# Schematic_v1_2.net
KiCad netlist of a schematic drawn in EasyEDA
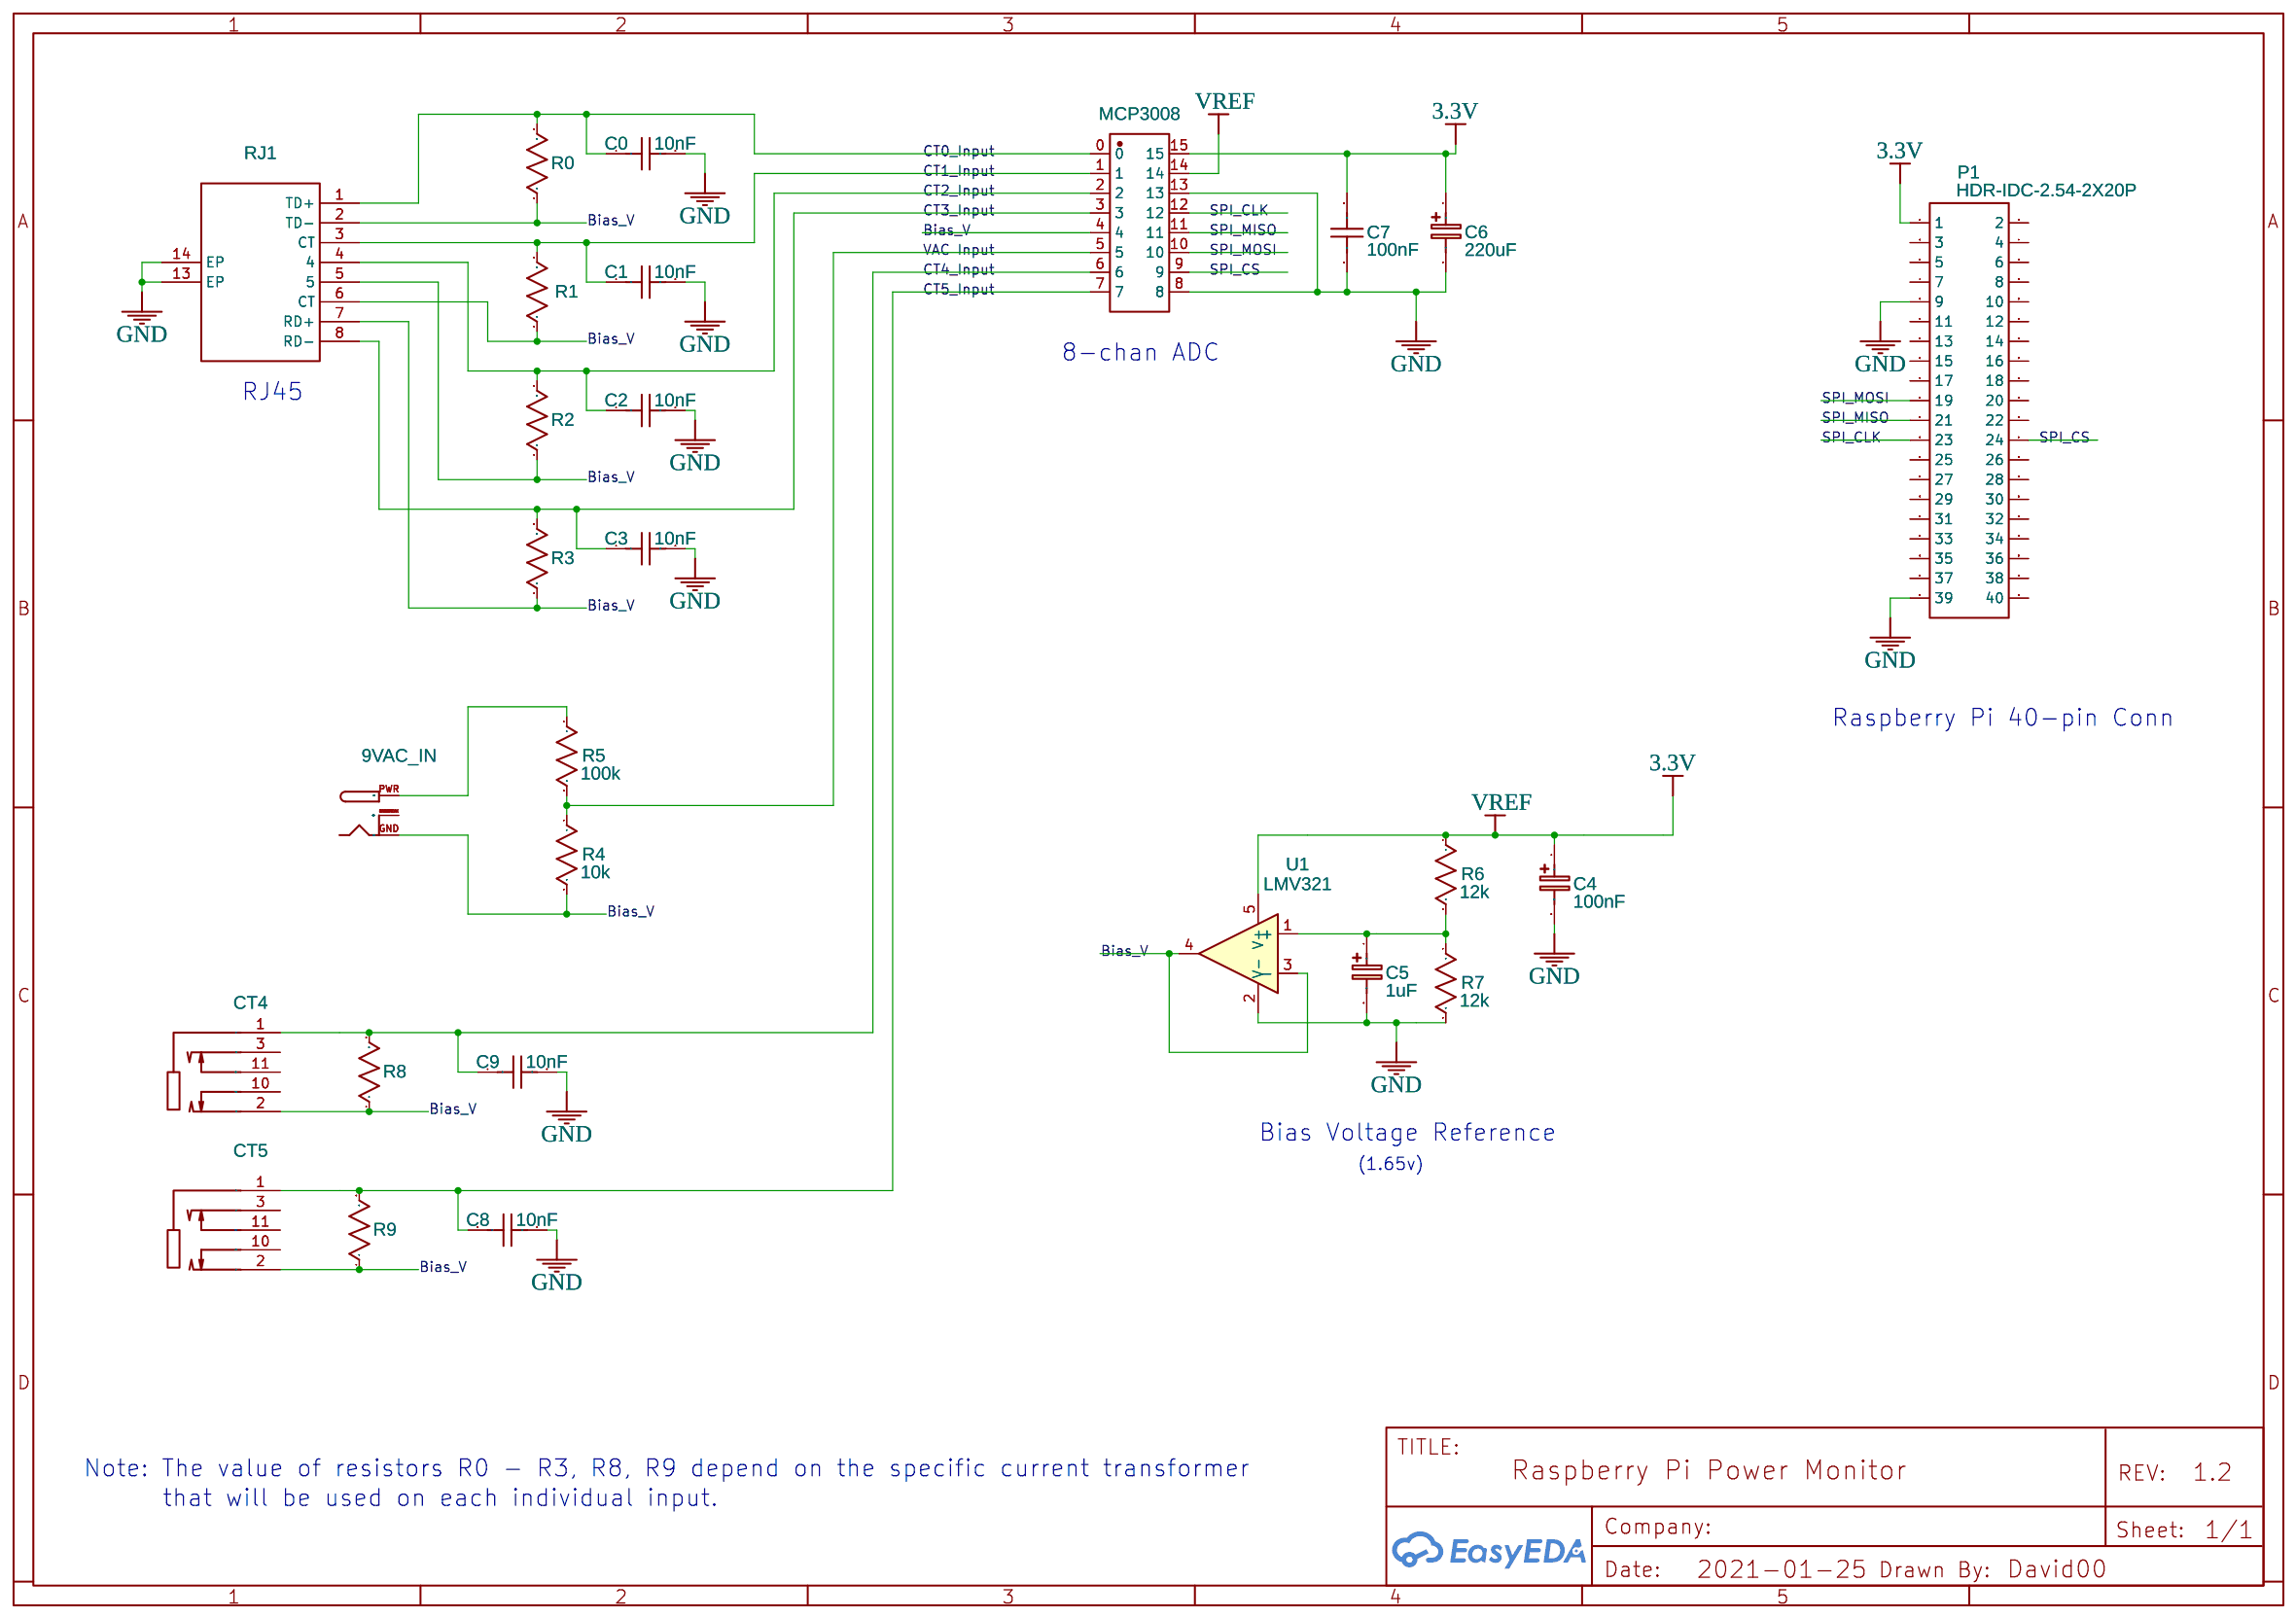
[diagram p0: schematic sheet]

(export (version "E")
  (design (tool "Eeschema 10.0.6"))
  (components
    (comp (ref "9VAC_IN") (value "DCBARRELPTH") (libsource (lib "") (part "DCBARRELPTH")))
    (comp (ref "C0")
      (value "10nF")
      (fields
        (field (name "BOM_Manufacturer Part") "PE103J2A0501")
        (field (name "BOM_Supplier Part") "C390168")
      )
      (libsource (lib "") (part "PE103J2A0501"))
    )
    (comp (ref "C1")
      (value "10nF")
      (fields
        (field (name "BOM_Manufacturer Part") "PE103J2A0501")
        (field (name "BOM_Supplier Part") "C390168")
      )
      (libsource (lib "") (part "PE103J2A0501"))
    )
    (comp (ref "C2")
      (value "10nF")
      (fields
        (field (name "BOM_Manufacturer Part") "PE103J2A0501")
        (field (name "BOM_Supplier Part") "C390168")
      )
      (libsource (lib "") (part "PE103J2A0501"))
    )
    (comp (ref "C3")
      (value "10nF")
      (fields
        (field (name "BOM_Manufacturer Part") "PE103J2A0501")
        (field (name "BOM_Supplier Part") "C390168")
      )
      (libsource (lib "") (part "PE103J2A0501"))
    )
    (comp (ref "C4") (value "100nF") (libsource (lib "") (part "Cap_Electrolytic(TH)_D3.0XF1.5_EU")))
    (comp (ref "C5") (value "1uF") (libsource (lib "") (part "Cap_Electrolytic(TH)_D3.0XF1.5_EU")))
    (comp (ref "C6") (value "220uF") (libsource (lib "") (part "Cap_Electrolytic(TH)_D3.0XF1.5_EU_1")))
    (comp (ref "C7")
      (value "100nF")
      (fields
        (field (name "BOM_Manufacturer Part") "CC45SL3AD101JYVNA")
        (field (name "BOM_Supplier Part") "C342396")
      )
      (libsource (lib "") (part "CC45SL3AD101JYVNA"))
    )
    (comp (ref "C8")
      (value "10nF")
      (fields
        (field (name "BOM_Manufacturer Part") "PE103J2A0501")
        (field (name "BOM_Supplier Part") "C390168")
      )
      (libsource (lib "") (part "PE103J2A0501_1"))
    )
    (comp (ref "C9")
      (value "10nF")
      (fields
        (field (name "BOM_Manufacturer Part") "PE103J2A0501")
        (field (name "BOM_Supplier Part") "C390168")
      )
      (libsource (lib "") (part "PE103J2A0501"))
    )
    (comp (ref "CT4")
      (value "PJ-328A0-B")
      (fields (field (name "BOM_Supplier Part") "C381129"))
      (libsource (lib "") (part "PJ-328A0-B"))
    )
    (comp (ref "CT5")
      (value "PJ-328A0-B")
      (fields (field (name "BOM_Supplier Part") "C381129"))
      (libsource (lib "") (part "PJ-328A0-B"))
    )
    (comp (ref "MCP3008")
      (value "IC seat 16P")
      (fields (field (name "BOM_Supplier Part") "C2326"))
      (libsource (lib "") (part "IC seat 16P"))
    )
    (comp (ref "P1")
      (value "HDR-IDC-2.54-2X20P")
      (fields
        (field (name "BOM_Manufacturer Part") "IDC Box 2X20 2.54MM")
        (field (name "BOM_Supplier Part") "C9138")
      )
      (libsource (lib "") (part "HDR-IDC-2.54-2X20P"))
    )
    (comp (ref "R0") (value "'") (libsource (lib "") (part "Res_AXIAL-0.3(1/8W)_US_1")))
    (comp (ref "R1") (value "'") (libsource (lib "") (part "Res_AXIAL-0.3(1/8W)_US_1")))
    (comp (ref "R2") (value "'") (libsource (lib "") (part "Res_AXIAL-0.3(1/8W)_US_1")))
    (comp (ref "R3") (value "'") (libsource (lib "") (part "Res_AXIAL-0.3(1/8W)_US_1")))
    (comp (ref "R4") (value "10k") (libsource (lib "") (part "Res_AXIAL-0.3(1/8W)_US")))
    (comp (ref "R5") (value "100k") (libsource (lib "") (part "Res_AXIAL-0.3(1/8W)_US")))
    (comp (ref "R6") (value "12k") (libsource (lib "") (part "Res_AXIAL-0.3(1/8W)_US")))
    (comp (ref "R7") (value "12k") (libsource (lib "") (part "Res_AXIAL-0.3(1/8W)_US")))
    (comp (ref "R8") (value "21") (libsource (lib "") (part "Res_AXIAL-0.3(1/8W)_US_1")))
    (comp (ref "R9") (value "21") (libsource (lib "") (part "Res_AXIAL-0.3(1/8W)_US_1")))
    (comp (ref "RJ1")
      (value "13F-62ANWA2NL")
      (fields (field (name "BOM_Supplier Part") "C179761"))
      (libsource (lib "") (part "13F-62ANWA2NL"))
    )
    (comp (ref "U1") (value "LMV321") (libsource (lib "") (part "LMV321")))
  )
  (nets
    (net (code "1") (name "/Bias_V") (class "Default")
      (node (ref "9VAC_IN") (pin "GND") (pinfunction "GND_GND") (pintype "passive"))
      (node (ref "CT4") (pin "2") (pinfunction "2_2") (pintype "unspecified"))
      (node (ref "CT5") (pin "2") (pinfunction "2_2") (pintype "unspecified"))
      (node (ref "MCP3008") (pin "4") (pinfunction "4_4") (pintype "unspecified"))
      (node (ref "R0") (pin "1") (pinfunction "1_1") (pintype "unspecified"))
      (node (ref "R1") (pin "1") (pinfunction "1_1") (pintype "unspecified"))
      (node (ref "R2") (pin "1") (pinfunction "1_1") (pintype "unspecified"))
      (node (ref "R3") (pin "1") (pinfunction "1_1") (pintype "unspecified"))
      (node (ref "R4") (pin "2") (pinfunction "2_2") (pintype "unspecified"))
      (node (ref "R8") (pin "1") (pinfunction "1_1") (pintype "unspecified"))
      (node (ref "R9") (pin "1") (pinfunction "1_1") (pintype "unspecified"))
      (node (ref "RJ1") (pin "2") (pinfunction "TD-_2") (pintype "unspecified"))
      (node (ref "RJ1") (pin "5") (pinfunction "5_5") (pintype "unspecified"))
      (node (ref "RJ1") (pin "6") (pinfunction "CT_6") (pintype "unspecified"))
      (node (ref "RJ1") (pin "7") (pinfunction "RD+_7") (pintype "unspecified"))
      (node (ref "U1") (pin "3") (pinfunction "-_3") (pintype "input"))
      (node (ref "U1") (pin "4") (pintype "output"))
    )
    (net (code "2") (name "/CT0_Input") (class "Default")
      (node (ref "C0") (pin "1") (pinfunction "1_1") (pintype "unspecified"))
      (node (ref "MCP3008") (pin "0") (pinfunction "0_0") (pintype "unspecified"))
      (node (ref "R0") (pin "2") (pinfunction "2_2") (pintype "unspecified"))
      (node (ref "RJ1") (pin "1") (pinfunction "TD+_1") (pintype "unspecified"))
    )
    (net (code "3") (name "/CT1_Input") (class "Default")
      (node (ref "C1") (pin "1") (pinfunction "1_1") (pintype "unspecified"))
      (node (ref "MCP3008") (pin "1") (pinfunction "1_1") (pintype "unspecified"))
      (node (ref "R1") (pin "2") (pinfunction "2_2") (pintype "unspecified"))
      (node (ref "RJ1") (pin "3") (pinfunction "CT_3") (pintype "unspecified"))
    )
    (net (code "4") (name "/CT2_Input") (class "Default")
      (node (ref "C2") (pin "1") (pinfunction "1_1") (pintype "unspecified"))
      (node (ref "MCP3008") (pin "2") (pinfunction "2_2") (pintype "unspecified"))
      (node (ref "R2") (pin "2") (pinfunction "2_2") (pintype "unspecified"))
      (node (ref "RJ1") (pin "4") (pinfunction "4_4") (pintype "unspecified"))
    )
    (net (code "5") (name "/CT3_Input") (class "Default")
      (node (ref "C3") (pin "1") (pinfunction "1_1") (pintype "unspecified"))
      (node (ref "MCP3008") (pin "3") (pinfunction "3_3") (pintype "unspecified"))
      (node (ref "R3") (pin "2") (pinfunction "2_2") (pintype "unspecified"))
      (node (ref "RJ1") (pin "8") (pinfunction "RD-_8") (pintype "unspecified"))
    )
    (net (code "6") (name "/CT4_Input") (class "Default")
      (node (ref "C9") (pin "1") (pinfunction "1_1") (pintype "unspecified"))
      (node (ref "CT4") (pin "1") (pinfunction "1_1") (pintype "unspecified"))
      (node (ref "MCP3008") (pin "6") (pinfunction "6_6") (pintype "unspecified"))
      (node (ref "R8") (pin "2") (pinfunction "2_2") (pintype "unspecified"))
    )
    (net (code "7") (name "/CT5_Input") (class "Default")
      (node (ref "C8") (pin "2") (pinfunction "2_2") (pintype "unspecified"))
      (node (ref "CT5") (pin "1") (pinfunction "1_1") (pintype "unspecified"))
      (node (ref "MCP3008") (pin "7") (pinfunction "7_7") (pintype "unspecified"))
      (node (ref "R9") (pin "2") (pinfunction "2_2") (pintype "unspecified"))
    )
    (net (code "8") (name "/SPI_CLK") (class "Default")
      (node (ref "MCP3008") (pin "12") (pinfunction "12_12") (pintype "unspecified"))
      (node (ref "P1") (pin "23") (pinfunction "23_23") (pintype "unspecified"))
    )
    (net (code "9") (name "/SPI_CS") (class "Default")
      (node (ref "MCP3008") (pin "9") (pinfunction "9_9") (pintype "unspecified"))
      (node (ref "P1") (pin "24") (pinfunction "24_24") (pintype "unspecified"))
    )
    (net (code "10") (name "/SPI_MISO") (class "Default")
      (node (ref "MCP3008") (pin "11") (pinfunction "11_11") (pintype "unspecified"))
      (node (ref "P1") (pin "21") (pinfunction "21_21") (pintype "unspecified"))
    )
    (net (code "11") (name "/SPI_MOSI") (class "Default")
      (node (ref "MCP3008") (pin "10") (pinfunction "10_10") (pintype "unspecified"))
      (node (ref "P1") (pin "19") (pinfunction "19_19") (pintype "unspecified"))
    )
    (net (code "12") (name "/VAC Input") (class "Default")
      (node (ref "MCP3008") (pin "5") (pinfunction "5_5") (pintype "unspecified"))
      (node (ref "R4") (pin "1") (pinfunction "1_1") (pintype "unspecified"))
      (node (ref "R5") (pin "2") (pinfunction "2_2") (pintype "unspecified"))
    )
    (net (code "13") (name "3.3V") (class "Default")
      (node (ref "C4") (pin "1") (pinfunction "1_1") (pintype "unspecified"))
      (node (ref "C6") (pin "1") (pinfunction "1_1") (pintype "unspecified"))
      (node (ref "C7") (pin "2") (pinfunction "2_2") (pintype "unspecified"))
      (node (ref "MCP3008") (pin "14") (pinfunction "14_14") (pintype "unspecified"))
      (node (ref "MCP3008") (pin "15") (pinfunction "15_15") (pintype "unspecified"))
      (node (ref "P1") (pin "1") (pinfunction "1_1") (pintype "unspecified"))
      (node (ref "R6") (pin "1") (pinfunction "1_1") (pintype "unspecified"))
      (node (ref "U1") (pin "5") (pinfunction "V+_5") (pintype "bidirectional"))
    )
    (net (code "14") (name "GND") (class "Default")
      (node (ref "C0") (pin "2") (pinfunction "2_2") (pintype "unspecified"))
      (node (ref "C1") (pin "2") (pinfunction "2_2") (pintype "unspecified"))
      (node (ref "C2") (pin "2") (pinfunction "2_2") (pintype "unspecified"))
      (node (ref "C3") (pin "2") (pinfunction "2_2") (pintype "unspecified"))
      (node (ref "C4") (pin "2") (pinfunction "2_2") (pintype "unspecified"))
      (node (ref "C5") (pin "2") (pinfunction "2_2") (pintype "unspecified"))
      (node (ref "C6") (pin "2") (pinfunction "2_2") (pintype "unspecified"))
      (node (ref "C7") (pin "1") (pinfunction "1_1") (pintype "unspecified"))
      (node (ref "C8") (pin "1") (pinfunction "1_1") (pintype "unspecified"))
      (node (ref "C9") (pin "2") (pinfunction "2_2") (pintype "unspecified"))
      (node (ref "MCP3008") (pin "13") (pinfunction "13_13") (pintype "unspecified"))
      (node (ref "MCP3008") (pin "8") (pinfunction "8_8") (pintype "unspecified"))
      (node (ref "P1") (pin "39") (pinfunction "39_39") (pintype "unspecified"))
      (node (ref "P1") (pin "9") (pinfunction "9_9") (pintype "unspecified"))
      (node (ref "R7") (pin "2") (pinfunction "2_2") (pintype "unspecified"))
      (node (ref "RJ1") (pin "13") (pinfunction "EP_13") (pintype "unspecified"))
      (node (ref "RJ1") (pin "14") (pinfunction "EP_14") (pintype "unspecified"))
      (node (ref "U1") (pin "2") (pinfunction "V-_2") (pintype "bidirectional"))
    )
    (net (code "15") (name "Net-(9VAC_IN-PadPWR)") (class "Default")
      (node (ref "9VAC_IN") (pin "PWR") (pinfunction "PWR_PWR") (pintype "passive"))
      (node (ref "R5") (pin "1") (pinfunction "1_1") (pintype "unspecified"))
    )
    (net (code "16") (name "Net-(U1-+)") (class "Default")
      (node (ref "C5") (pin "1") (pinfunction "1_1") (pintype "unspecified"))
      (node (ref "R6") (pin "2") (pinfunction "2_2") (pintype "unspecified"))
      (node (ref "R7") (pin "1") (pinfunction "1_1") (pintype "unspecified"))
      (node (ref "U1") (pin "1") (pinfunction "+_1") (pintype "input"))
    )
    (net (code "17") (name "unconnected-(9VAC_IN-PadGNDBREAK)") (class "Default")
      (node (ref "9VAC_IN") (pin "GNDBREAK") (pinfunction "GNDBREAK_GNDBREAK") (pintype "passive"))
    )
    (net (code "18") (name "unconnected-(CT4-Pad3)") (class "Default")
      (node (ref "CT4") (pin "3") (pinfunction "3_3") (pintype "unspecified"))
    )
    (net (code "19") (name "unconnected-(CT4-Pad10)") (class "Default")
      (node (ref "CT4") (pin "10") (pinfunction "10_10") (pintype "unspecified"))
    )
    (net (code "20") (name "unconnected-(CT4-Pad11)") (class "Default")
      (node (ref "CT4") (pin "11") (pinfunction "11_11") (pintype "unspecified"))
    )
    (net (code "21") (name "unconnected-(CT5-Pad3)") (class "Default")
      (node (ref "CT5") (pin "3") (pinfunction "3_3") (pintype "unspecified"))
    )
    (net (code "22") (name "unconnected-(CT5-Pad10)") (class "Default")
      (node (ref "CT5") (pin "10") (pinfunction "10_10") (pintype "unspecified"))
    )
    (net (code "23") (name "unconnected-(CT5-Pad11)") (class "Default")
      (node (ref "CT5") (pin "11") (pinfunction "11_11") (pintype "unspecified"))
    )
    (net (code "24") (name "unconnected-(P1-Pad2)") (class "Default")
      (node (ref "P1") (pin "2") (pinfunction "2_2") (pintype "unspecified"))
    )
    (net (code "25") (name "unconnected-(P1-Pad3)") (class "Default")
      (node (ref "P1") (pin "3") (pinfunction "3_3") (pintype "unspecified"))
    )
    (net (code "26") (name "unconnected-(P1-Pad4)") (class "Default")
      (node (ref "P1") (pin "4") (pinfunction "4_4") (pintype "unspecified"))
    )
    (net (code "27") (name "unconnected-(P1-Pad5)") (class "Default")
      (node (ref "P1") (pin "5") (pinfunction "5_5") (pintype "unspecified"))
    )
    (net (code "28") (name "unconnected-(P1-Pad6)") (class "Default")
      (node (ref "P1") (pin "6") (pinfunction "6_6") (pintype "unspecified"))
    )
    (net (code "29") (name "unconnected-(P1-Pad7)") (class "Default")
      (node (ref "P1") (pin "7") (pinfunction "7_7") (pintype "unspecified"))
    )
    (net (code "30") (name "unconnected-(P1-Pad8)") (class "Default")
      (node (ref "P1") (pin "8") (pinfunction "8_8") (pintype "unspecified"))
    )
    (net (code "31") (name "unconnected-(P1-Pad10)") (class "Default")
      (node (ref "P1") (pin "10") (pinfunction "10_10") (pintype "unspecified"))
    )
    (net (code "32") (name "unconnected-(P1-Pad11)") (class "Default")
      (node (ref "P1") (pin "11") (pinfunction "11_11") (pintype "unspecified"))
    )
    (net (code "33") (name "unconnected-(P1-Pad12)") (class "Default")
      (node (ref "P1") (pin "12") (pinfunction "12_12") (pintype "unspecified"))
    )
    (net (code "34") (name "unconnected-(P1-Pad13)") (class "Default")
      (node (ref "P1") (pin "13") (pinfunction "13_13") (pintype "unspecified"))
    )
    (net (code "35") (name "unconnected-(P1-Pad14)") (class "Default")
      (node (ref "P1") (pin "14") (pinfunction "14_14") (pintype "unspecified"))
    )
    (net (code "36") (name "unconnected-(P1-Pad15)") (class "Default")
      (node (ref "P1") (pin "15") (pinfunction "15_15") (pintype "unspecified"))
    )
    (net (code "37") (name "unconnected-(P1-Pad16)") (class "Default")
      (node (ref "P1") (pin "16") (pinfunction "16_16") (pintype "unspecified"))
    )
    (net (code "38") (name "unconnected-(P1-Pad17)") (class "Default")
      (node (ref "P1") (pin "17") (pinfunction "17_17") (pintype "unspecified"))
    )
    (net (code "39") (name "unconnected-(P1-Pad18)") (class "Default")
      (node (ref "P1") (pin "18") (pinfunction "18_18") (pintype "unspecified"))
    )
    (net (code "40") (name "unconnected-(P1-Pad20)") (class "Default")
      (node (ref "P1") (pin "20") (pinfunction "20_20") (pintype "unspecified"))
    )
    (net (code "41") (name "unconnected-(P1-Pad22)") (class "Default")
      (node (ref "P1") (pin "22") (pinfunction "22_22") (pintype "unspecified"))
    )
    (net (code "42") (name "unconnected-(P1-Pad25)") (class "Default")
      (node (ref "P1") (pin "25") (pinfunction "25_25") (pintype "unspecified"))
    )
    (net (code "43") (name "unconnected-(P1-Pad26)") (class "Default")
      (node (ref "P1") (pin "26") (pinfunction "26_26") (pintype "unspecified"))
    )
    (net (code "44") (name "unconnected-(P1-Pad27)") (class "Default")
      (node (ref "P1") (pin "27") (pinfunction "27_27") (pintype "unspecified"))
    )
    (net (code "45") (name "unconnected-(P1-Pad28)") (class "Default")
      (node (ref "P1") (pin "28") (pinfunction "28_28") (pintype "unspecified"))
    )
    (net (code "46") (name "unconnected-(P1-Pad29)") (class "Default")
      (node (ref "P1") (pin "29") (pinfunction "29_29") (pintype "unspecified"))
    )
    (net (code "47") (name "unconnected-(P1-Pad30)") (class "Default")
      (node (ref "P1") (pin "30") (pinfunction "30_30") (pintype "unspecified"))
    )
    (net (code "48") (name "unconnected-(P1-Pad31)") (class "Default")
      (node (ref "P1") (pin "31") (pinfunction "31_31") (pintype "unspecified"))
    )
    (net (code "49") (name "unconnected-(P1-Pad32)") (class "Default")
      (node (ref "P1") (pin "32") (pinfunction "32_32") (pintype "unspecified"))
    )
    (net (code "50") (name "unconnected-(P1-Pad33)") (class "Default")
      (node (ref "P1") (pin "33") (pinfunction "33_33") (pintype "unspecified"))
    )
    (net (code "51") (name "unconnected-(P1-Pad34)") (class "Default")
      (node (ref "P1") (pin "34") (pinfunction "34_34") (pintype "unspecified"))
    )
    (net (code "52") (name "unconnected-(P1-Pad35)") (class "Default")
      (node (ref "P1") (pin "35") (pinfunction "35_35") (pintype "unspecified"))
    )
    (net (code "53") (name "unconnected-(P1-Pad36)") (class "Default")
      (node (ref "P1") (pin "36") (pinfunction "36_36") (pintype "unspecified"))
    )
    (net (code "54") (name "unconnected-(P1-Pad37)") (class "Default")
      (node (ref "P1") (pin "37") (pinfunction "37_37") (pintype "unspecified"))
    )
    (net (code "55") (name "unconnected-(P1-Pad38)") (class "Default")
      (node (ref "P1") (pin "38") (pinfunction "38_38") (pintype "unspecified"))
    )
    (net (code "56") (name "unconnected-(P1-Pad40)") (class "Default")
      (node (ref "P1") (pin "40") (pinfunction "40_40") (pintype "unspecified"))
    )
  )
)
